# control_psw.net
KiCad netlist of a schematic drawn in EAGLE
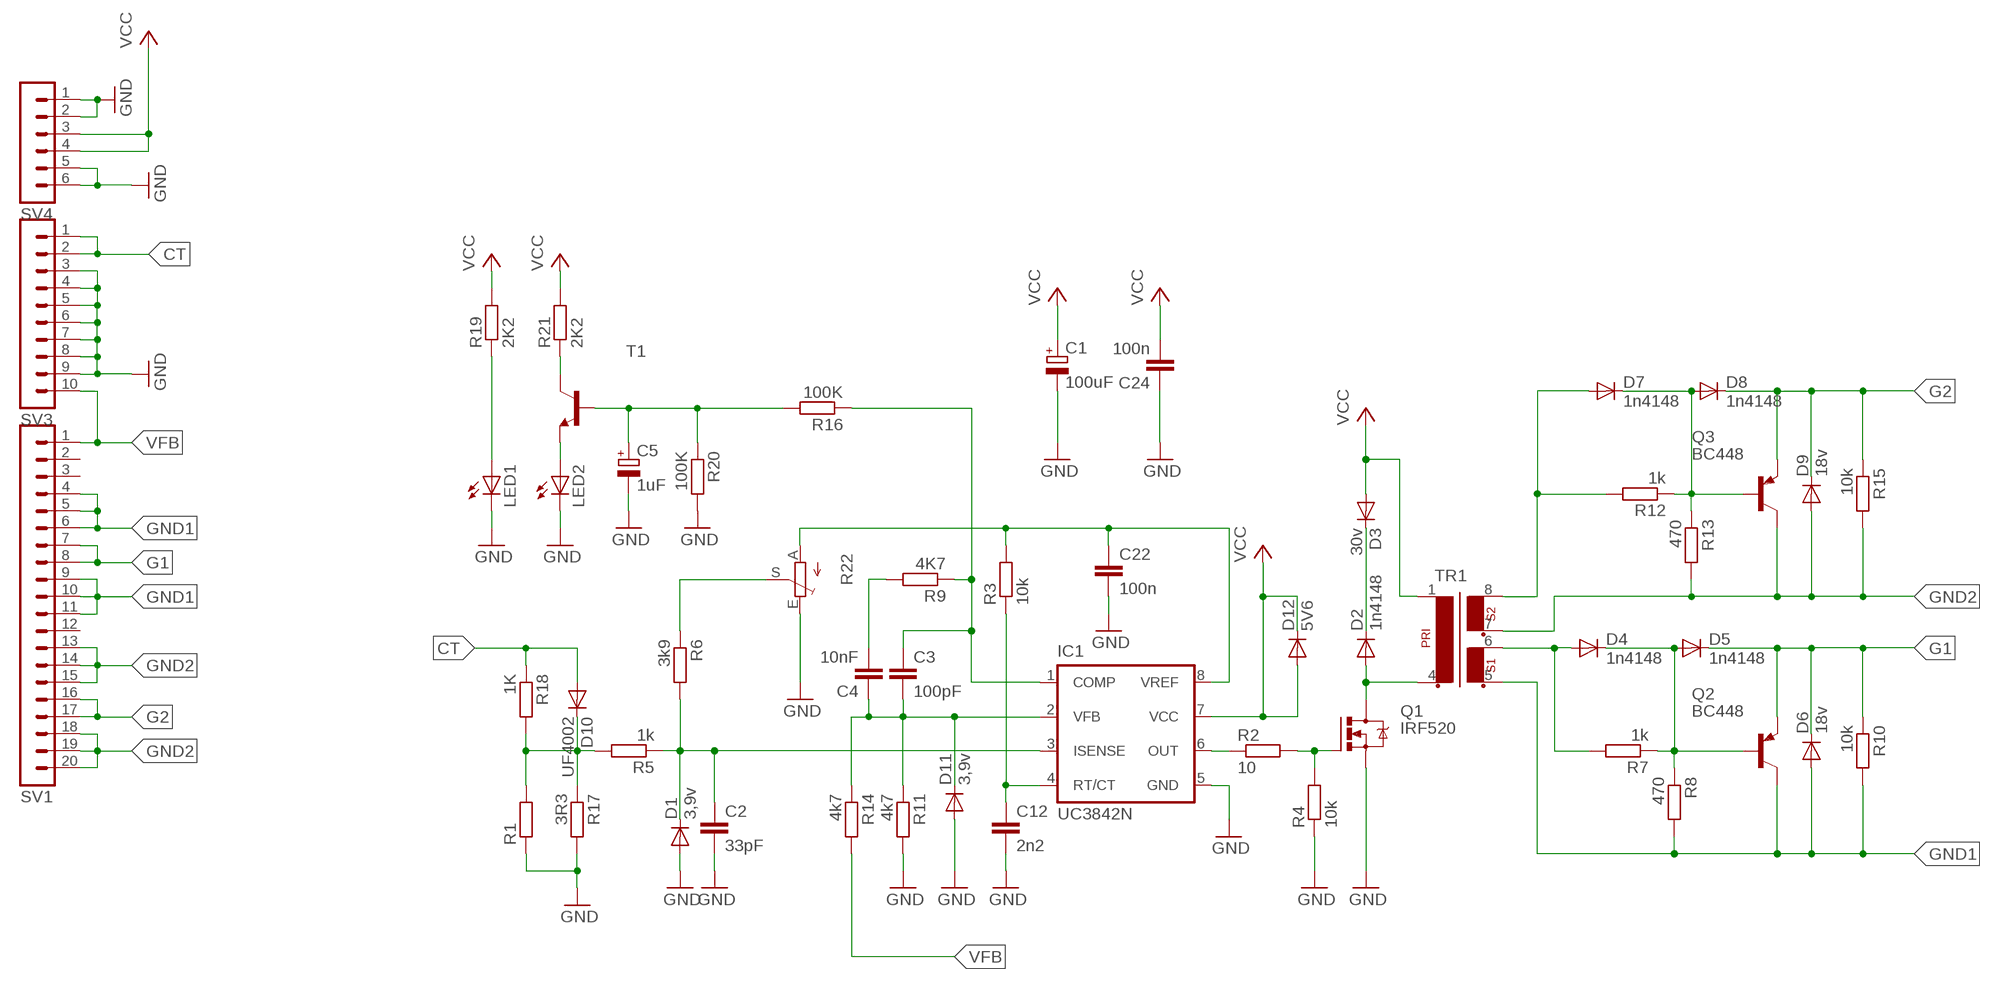
[diagram p0: schematic, sheet 1]

(export (version "E")
  (design (tool "Eeschema 10.0.6"))
  (components
    (comp (ref "C1")
      (value "100uF")
      (footprint "eagle-import:E5-6")
      (libsource (lib "eagle-import") (part "CPOL-EUE5-6"))
    )
    (comp (ref "C2")
      (value "33pF")
      (footprint "eagle-import:C050-025X075")
      (libsource (lib "eagle-import") (part "C-EU050-025X075"))
    )
    (comp (ref "C3")
      (value "100pF")
      (footprint "eagle-import:C050-025X075")
      (libsource (lib "eagle-import") (part "C-EU050-025X075"))
    )
    (comp (ref "C4")
      (value "10nF")
      (footprint "eagle-import:C050-025X075")
      (libsource (lib "eagle-import") (part "C-EU050-025X075"))
    )
    (comp (ref "C5")
      (value "1uF")
      (footprint "eagle-import:E5-6")
      (libsource (lib "eagle-import") (part "CPOL-EUE5-6"))
    )
    (comp (ref "C12")
      (value "2n2")
      (footprint "eagle-import:C050-025X075")
      (libsource (lib "eagle-import") (part "C-EU050-025X075"))
    )
    (comp (ref "C22")
      (value "100n")
      (footprint "eagle-import:C050-025X075")
      (libsource (lib "eagle-import") (part "C-EU050-025X075"))
    )
    (comp (ref "C24")
      (value "100n")
      (footprint "eagle-import:C050-025X075")
      (libsource (lib "eagle-import") (part "C-EU050-025X075"))
    )
    (comp (ref "D1")
      (value "3,9v")
      (footprint "eagle-import:DO35-10")
      (libsource (lib "eagle-import") (part "1N4446"))
    )
    (comp (ref "D2")
      (value "1n4148")
      (footprint "eagle-import:DO35-10")
      (libsource (lib "eagle-import") (part "1N4446"))
    )
    (comp (ref "D3")
      (value "30v")
      (footprint "eagle-import:DO35-10")
      (libsource (lib "eagle-import") (part "1N4446"))
    )
    (comp (ref "D4")
      (value "1n4148")
      (footprint "eagle-import:DO35-10")
      (libsource (lib "eagle-import") (part "1N4446"))
    )
    (comp (ref "D5")
      (value "1n4148")
      (footprint "eagle-import:DO35-10")
      (libsource (lib "eagle-import") (part "1N4446"))
    )
    (comp (ref "D6")
      (value "18v")
      (footprint "eagle-import:DO35-10")
      (libsource (lib "eagle-import") (part "1N4446"))
    )
    (comp (ref "D7")
      (value "1n4148")
      (footprint "eagle-import:DO35-10")
      (libsource (lib "eagle-import") (part "1N4446"))
    )
    (comp (ref "D8")
      (value "1n4148")
      (footprint "eagle-import:DO35-10")
      (libsource (lib "eagle-import") (part "1N4446"))
    )
    (comp (ref "D9")
      (value "18v")
      (footprint "eagle-import:DO35-10")
      (libsource (lib "eagle-import") (part "1N4446"))
    )
    (comp (ref "D10")
      (value "UF4002")
      (footprint "eagle-import:DO35-10")
      (libsource (lib "eagle-import") (part "1N4446"))
    )
    (comp (ref "D11")
      (value "3,9v")
      (footprint "eagle-import:DO35-10")
      (libsource (lib "eagle-import") (part "1N4446"))
    )
    (comp (ref "D12")
      (value "5V6")
      (footprint "eagle-import:DO35-10")
      (libsource (lib "eagle-import") (part "1N4446"))
    )
    (comp (ref "IC1")
      (value "UC3842N")
      (footprint "eagle-import:DIL08")
      (libsource (lib "eagle-import") (part "UC384N2"))
    )
    (comp (ref "LED1")
      (value "LED5MM")
      (footprint "eagle-import:LED5MM")
      (libsource (lib "eagle-import") (part "LED5MM"))
    )
    (comp (ref "LED2")
      (value "LED5MM")
      (footprint "eagle-import:LED5MM")
      (libsource (lib "eagle-import") (part "LED5MM"))
    )
    (comp (ref "Q1")
      (value "IRF520")
      (footprint "eagle-import:TO220BV")
      (libsource (lib "eagle-import") (part "IRF520"))
    )
    (comp (ref "Q2")
      (value "BC448")
      (footprint "eagle-import:TO92-EBC")
      (libsource (lib "eagle-import") (part "BC448"))
    )
    (comp (ref "Q3")
      (value "BC448")
      (footprint "eagle-import:TO92-EBC")
      (libsource (lib "eagle-import") (part "BC448"))
    )
    (comp (ref "R1")
      (value "R-EU_0411/12")
      (footprint "eagle-import:0411_12")
      (libsource (lib "eagle-import") (part "R-EU_0411/12"))
    )
    (comp (ref "R2")
      (value "10")
      (footprint "eagle-import:0207_10")
      (libsource (lib "eagle-import") (part "R-EU_0207/10"))
    )
    (comp (ref "R3")
      (value "10k")
      (footprint "eagle-import:0207_10")
      (libsource (lib "eagle-import") (part "R-EU_0207/10"))
    )
    (comp (ref "R4")
      (value "10k")
      (footprint "eagle-import:0207_10")
      (libsource (lib "eagle-import") (part "R-EU_0207/10"))
    )
    (comp (ref "R5")
      (value "1k")
      (footprint "eagle-import:0207_10")
      (libsource (lib "eagle-import") (part "R-EU_0207/10"))
    )
    (comp (ref "R6")
      (value "3k9")
      (footprint "eagle-import:0207_10")
      (libsource (lib "eagle-import") (part "R-EU_0207/10"))
    )
    (comp (ref "R7")
      (value "1k")
      (footprint "eagle-import:0207_10")
      (libsource (lib "eagle-import") (part "R-EU_0207/10"))
    )
    (comp (ref "R8")
      (value "470")
      (footprint "eagle-import:0207_10")
      (libsource (lib "eagle-import") (part "R-EU_0207/10"))
    )
    (comp (ref "R9")
      (value "4K7")
      (footprint "eagle-import:0207_10")
      (libsource (lib "eagle-import") (part "R-EU_0207/10"))
    )
    (comp (ref "R10")
      (value "10k")
      (footprint "eagle-import:0207_10")
      (libsource (lib "eagle-import") (part "R-EU_0207/10"))
    )
    (comp (ref "R11")
      (value "4k7")
      (footprint "eagle-import:0207_10")
      (libsource (lib "eagle-import") (part "R-EU_0207/10"))
    )
    (comp (ref "R12")
      (value "1k")
      (footprint "eagle-import:0207_10")
      (libsource (lib "eagle-import") (part "R-EU_0207/10"))
    )
    (comp (ref "R13")
      (value "470")
      (footprint "eagle-import:0207_10")
      (libsource (lib "eagle-import") (part "R-EU_0207/10"))
    )
    (comp (ref "R14")
      (value "4k7")
      (footprint "eagle-import:0207_10")
      (libsource (lib "eagle-import") (part "R-EU_0207/10"))
    )
    (comp (ref "R15")
      (value "10k")
      (footprint "eagle-import:0207_10")
      (libsource (lib "eagle-import") (part "R-EU_0207/10"))
    )
    (comp (ref "R16")
      (value "100K")
      (footprint "eagle-import:0207_10")
      (libsource (lib "eagle-import") (part "R-EU_0207/10"))
    )
    (comp (ref "R17")
      (value "3R3")
      (footprint "eagle-import:0207_10")
      (libsource (lib "eagle-import") (part "R-EU_0207/10"))
    )
    (comp (ref "R18")
      (value "1K")
      (footprint "eagle-import:0207_10")
      (libsource (lib "eagle-import") (part "R-EU_0207/10"))
    )
    (comp (ref "R19")
      (value "2K2")
      (footprint "eagle-import:0207_10")
      (libsource (lib "eagle-import") (part "R-EU_0207/10"))
    )
    (comp (ref "R20")
      (value "100K")
      (footprint "eagle-import:0207_10")
      (libsource (lib "eagle-import") (part "R-EU_0207/10"))
    )
    (comp (ref "R21")
      (value "2K2")
      (footprint "eagle-import:0207_10")
      (libsource (lib "eagle-import") (part "R-EU_0207/10"))
    )
    (comp (ref "R22")
      (value "TRIM_EU-RJ9W")
      (footprint "eagle-import:RJ9W")
      (libsource (lib "eagle-import") (part "TRIM_EU-RJ9W"))
    )
    (comp (ref "SV1")
      (value "MA20-1")
      (footprint "eagle-import:MA20-1")
      (libsource (lib "eagle-import") (part "MA20-1"))
    )
    (comp (ref "SV3")
      (value "MA10-1")
      (footprint "eagle-import:MA10-1")
      (libsource (lib "eagle-import") (part "MA10-1"))
    )
    (comp (ref "SV4")
      (value "MA06-1")
      (footprint "eagle-import:MA06-1")
      (libsource (lib "eagle-import") (part "MA06-1"))
    )
    (comp (ref "T1")
      (value "BC547-NPN-TO92-CBE")
      (footprint "eagle-import:TO92-CBE")
      (libsource (lib "eagle-import") (part "-NPN-TO92-CBEBC547"))
    )
    (comp (ref "TR1")
      (value "EE20-2")
      (footprint "eagle-import:EE20-2")
      (libsource (lib "eagle-import") (part "EE20-2"))
    )
  )
  (nets
    (net (code "1") (name "CT") (class "Default")
      (node (ref "D10") (pin "A") (pinfunction "A_A") (pintype "passive"))
      (node (ref "R18") (pin "1") (pinfunction "1_1") (pintype "passive"))
      (node (ref "SV3") (pin "1") (pinfunction "1_1") (pintype "passive"))
      (node (ref "SV3") (pin "2") (pinfunction "2_2") (pintype "passive"))
    )
    (net (code "2") (name "G1") (class "Default")
      (node (ref "D5") (pin "C") (pinfunction "C_C") (pintype "passive"))
      (node (ref "D6") (pin "C") (pinfunction "C_C") (pintype "passive"))
      (node (ref "Q2") (pin "E") (pinfunction "E_E") (pintype "passive"))
      (node (ref "R10") (pin "1") (pinfunction "1_1") (pintype "passive"))
      (node (ref "SV1") (pin "7") (pinfunction "7_7") (pintype "passive"))
      (node (ref "SV1") (pin "8") (pinfunction "8_8") (pintype "passive"))
    )
    (net (code "3") (name "G2") (class "Default")
      (node (ref "D8") (pin "C") (pinfunction "C_C") (pintype "passive"))
      (node (ref "D9") (pin "C") (pinfunction "C_C") (pintype "passive"))
      (node (ref "Q3") (pin "E") (pinfunction "E_E") (pintype "passive"))
      (node (ref "R15") (pin "1") (pinfunction "1_1") (pintype "passive"))
      (node (ref "SV1") (pin "16") (pinfunction "16_16") (pintype "passive"))
      (node (ref "SV1") (pin "17") (pinfunction "17_17") (pintype "passive"))
    )
    (net (code "4") (name "GND") (class "Default")
      (node (ref "C1") (pin "-") (pinfunction "-_-") (pintype "passive"))
      (node (ref "C12") (pin "2") (pinfunction "2_2") (pintype "passive"))
      (node (ref "C2") (pin "2") (pinfunction "2_2") (pintype "passive"))
      (node (ref "C22") (pin "2") (pinfunction "2_2") (pintype "passive"))
      (node (ref "C24") (pin "1") (pinfunction "1_1") (pintype "passive"))
      (node (ref "C5") (pin "-") (pinfunction "-_-") (pintype "passive"))
      (node (ref "D1") (pin "A") (pinfunction "A_A") (pintype "passive"))
      (node (ref "D11") (pin "A") (pinfunction "A_A") (pintype "passive"))
      (node (ref "IC1") (pin "5") (pinfunction "GND_5") (pintype "power_in"))
      (node (ref "LED1") (pin "K") (pinfunction "C_K") (pintype "passive"))
      (node (ref "LED2") (pin "K") (pinfunction "C_K") (pintype "passive"))
      (node (ref "Q1") (pin "S") (pinfunction "S_S") (pintype "passive"))
      (node (ref "R1") (pin "1") (pinfunction "1_1") (pintype "passive"))
      (node (ref "R11") (pin "2") (pinfunction "2_2") (pintype "passive"))
      (node (ref "R17") (pin "2") (pinfunction "2_2") (pintype "passive"))
      (node (ref "R20") (pin "2") (pinfunction "2_2") (pintype "passive"))
      (node (ref "R22") (pin "E") (pinfunction "E_E") (pintype "passive"))
      (node (ref "R4") (pin "1") (pinfunction "1_1") (pintype "passive"))
      (node (ref "SV3") (pin "3") (pinfunction "3_3") (pintype "passive"))
      (node (ref "SV3") (pin "4") (pinfunction "4_4") (pintype "passive"))
      (node (ref "SV3") (pin "5") (pinfunction "5_5") (pintype "passive"))
      (node (ref "SV3") (pin "6") (pinfunction "6_6") (pintype "passive"))
      (node (ref "SV3") (pin "7") (pinfunction "7_7") (pintype "passive"))
      (node (ref "SV3") (pin "8") (pinfunction "8_8") (pintype "passive"))
      (node (ref "SV3") (pin "9") (pinfunction "9_9") (pintype "passive"))
      (node (ref "SV4") (pin "1") (pinfunction "1_1") (pintype "passive"))
      (node (ref "SV4") (pin "2") (pinfunction "2_2") (pintype "passive"))
      (node (ref "SV4") (pin "5") (pinfunction "5_5") (pintype "passive"))
      (node (ref "SV4") (pin "6") (pinfunction "6_6") (pintype "passive"))
    )
    (net (code "5") (name "GND1") (class "Default")
      (node (ref "D6") (pin "A") (pinfunction "A_A") (pintype "passive"))
      (node (ref "Q2") (pin "C") (pinfunction "C_C") (pintype "passive"))
      (node (ref "R10") (pin "2") (pinfunction "2_2") (pintype "passive"))
      (node (ref "R8") (pin "2") (pinfunction "2_2") (pintype "passive"))
      (node (ref "SV1") (pin "10") (pinfunction "10_10") (pintype "passive"))
      (node (ref "SV1") (pin "11") (pinfunction "11_11") (pintype "passive"))
      (node (ref "SV1") (pin "4") (pinfunction "4_4") (pintype "passive"))
      (node (ref "SV1") (pin "5") (pinfunction "5_5") (pintype "passive"))
      (node (ref "SV1") (pin "6") (pinfunction "6_6") (pintype "passive"))
      (node (ref "SV1") (pin "9") (pinfunction "9_9") (pintype "passive"))
      (node (ref "TR1") (pin "5") (pinfunction "3_5") (pintype "passive"))
    )
    (net (code "6") (name "GND2") (class "Default")
      (node (ref "D9") (pin "A") (pinfunction "A_A") (pintype "passive"))
      (node (ref "Q3") (pin "C") (pinfunction "C_C") (pintype "passive"))
      (node (ref "R13") (pin "2") (pinfunction "2_2") (pintype "passive"))
      (node (ref "R15") (pin "2") (pinfunction "2_2") (pintype "passive"))
      (node (ref "SV1") (pin "13") (pinfunction "13_13") (pintype "passive"))
      (node (ref "SV1") (pin "14") (pinfunction "14_14") (pintype "passive"))
      (node (ref "SV1") (pin "15") (pinfunction "15_15") (pintype "passive"))
      (node (ref "SV1") (pin "18") (pinfunction "18_18") (pintype "passive"))
      (node (ref "SV1") (pin "19") (pinfunction "19_19") (pintype "passive"))
      (node (ref "SV1") (pin "20") (pinfunction "20_20") (pintype "passive"))
      (node (ref "TR1") (pin "7") (pinfunction "5_7") (pintype "passive"))
    )
    (net (code "7") (name "Net-(C4-Pad2)") (class "Default")
      (node (ref "C4") (pin "2") (pinfunction "2_2") (pintype "passive"))
      (node (ref "R9") (pin "2") (pinfunction "2_2") (pintype "passive"))
    )
    (net (code "8") (name "Net-(C5-Pad+)") (class "Default")
      (node (ref "C5") (pin "+") (pinfunction "+_+") (pintype "passive"))
      (node (ref "R16") (pin "2") (pinfunction "2_2") (pintype "passive"))
      (node (ref "R20") (pin "1") (pinfunction "1_1") (pintype "passive"))
      (node (ref "T1") (pin "B") (pinfunction "B_B") (pintype "passive"))
    )
    (net (code "9") (name "Net-(D2-PadC)") (class "Default")
      (node (ref "D2") (pin "C") (pinfunction "C_C") (pintype "passive"))
      (node (ref "D3") (pin "C") (pinfunction "C_C") (pintype "passive"))
    )
    (net (code "10") (name "Net-(D4-PadC)") (class "Default")
      (node (ref "D4") (pin "C") (pinfunction "C_C") (pintype "passive"))
      (node (ref "D5") (pin "A") (pinfunction "A_A") (pintype "passive"))
      (node (ref "Q2") (pin "B") (pinfunction "B_B") (pintype "passive"))
      (node (ref "R7") (pin "1") (pinfunction "1_1") (pintype "passive"))
      (node (ref "R8") (pin "1") (pinfunction "1_1") (pintype "passive"))
    )
    (net (code "11") (name "Net-(D7-PadC)") (class "Default")
      (node (ref "D7") (pin "C") (pinfunction "C_C") (pintype "passive"))
      (node (ref "D8") (pin "A") (pinfunction "A_A") (pintype "passive"))
      (node (ref "Q3") (pin "B") (pinfunction "B_B") (pintype "passive"))
      (node (ref "R12") (pin "1") (pinfunction "1_1") (pintype "passive"))
      (node (ref "R13") (pin "1") (pinfunction "1_1") (pintype "passive"))
    )
    (net (code "12") (name "Net-(D10-PadC)") (class "Default")
      (node (ref "D10") (pin "C") (pinfunction "C_C") (pintype "passive"))
      (node (ref "R1") (pin "2") (pinfunction "2_2") (pintype "passive"))
      (node (ref "R17") (pin "1") (pinfunction "1_1") (pintype "passive"))
      (node (ref "R18") (pin "2") (pinfunction "2_2") (pintype "passive"))
      (node (ref "R5") (pin "2") (pinfunction "2_2") (pintype "passive"))
    )
    (net (code "13") (name "Net-(IC1-COMP)") (class "Default")
      (node (ref "C3") (pin "1") (pinfunction "1_1") (pintype "passive"))
      (node (ref "IC1") (pin "1") (pinfunction "COMP_1") (pintype "passive"))
      (node (ref "R16") (pin "1") (pinfunction "1_1") (pintype "passive"))
      (node (ref "R9") (pin "1") (pinfunction "1_1") (pintype "passive"))
    )
    (net (code "14") (name "Net-(IC1-ISENSE)") (class "Default")
      (node (ref "C2") (pin "1") (pinfunction "1_1") (pintype "passive"))
      (node (ref "D1") (pin "C") (pinfunction "C_C") (pintype "passive"))
      (node (ref "IC1") (pin "3") (pinfunction "ISENSE_3") (pintype "input"))
      (node (ref "R5") (pin "1") (pinfunction "1_1") (pintype "passive"))
      (node (ref "R6") (pin "2") (pinfunction "2_2") (pintype "passive"))
    )
    (net (code "15") (name "Net-(IC1-OUT)") (class "Default")
      (node (ref "IC1") (pin "6") (pinfunction "OUT_6") (pintype "output"))
      (node (ref "R2") (pin "1") (pinfunction "1_1") (pintype "passive"))
    )
    (net (code "16") (name "Net-(IC1-RT{slash}CT)") (class "Default")
      (node (ref "C12") (pin "1") (pinfunction "1_1") (pintype "passive"))
      (node (ref "IC1") (pin "4") (pinfunction "RT/CT_4") (pintype "passive"))
      (node (ref "R3") (pin "1") (pinfunction "1_1") (pintype "passive"))
    )
    (net (code "17") (name "Net-(IC1-VFB)") (class "Default")
      (node (ref "C3") (pin "2") (pinfunction "2_2") (pintype "passive"))
      (node (ref "C4") (pin "1") (pinfunction "1_1") (pintype "passive"))
      (node (ref "D11") (pin "C") (pinfunction "C_C") (pintype "passive"))
      (node (ref "IC1") (pin "2") (pinfunction "VFB_2") (pintype "input"))
      (node (ref "R11") (pin "1") (pinfunction "1_1") (pintype "passive"))
      (node (ref "R14") (pin "1") (pinfunction "1_1") (pintype "passive"))
    )
    (net (code "18") (name "Net-(IC1-VREF)") (class "Default")
      (node (ref "C22") (pin "1") (pinfunction "1_1") (pintype "passive"))
      (node (ref "IC1") (pin "8") (pinfunction "VREF_8") (pintype "passive"))
      (node (ref "R22") (pin "A") (pinfunction "A_A") (pintype "passive"))
      (node (ref "R3") (pin "2") (pinfunction "2_2") (pintype "passive"))
    )
    (net (code "19") (name "Net-(LED1-PadA)") (class "Default")
      (node (ref "LED1") (pin "A") (pinfunction "A_A") (pintype "passive"))
      (node (ref "R19") (pin "1") (pinfunction "1_1") (pintype "passive"))
    )
    (net (code "20") (name "Net-(LED2-PadA)") (class "Default")
      (node (ref "LED2") (pin "A") (pinfunction "A_A") (pintype "passive"))
      (node (ref "T1") (pin "E") (pinfunction "E_E") (pintype "passive"))
    )
    (net (code "21") (name "Net-(Q1-PadG)") (class "Default")
      (node (ref "Q1") (pin "G") (pinfunction "G_G") (pintype "passive"))
      (node (ref "R2") (pin "2") (pinfunction "2_2") (pintype "passive"))
      (node (ref "R4") (pin "2") (pinfunction "2_2") (pintype "passive"))
    )
    (net (code "22") (name "Net-(R21-Pad1)") (class "Default")
      (node (ref "R21") (pin "1") (pinfunction "1_1") (pintype "passive"))
      (node (ref "T1") (pin "C") (pinfunction "C_C") (pintype "passive"))
    )
    (net (code "23") (name "Net-(R22-PadS)") (class "Default")
      (node (ref "R22") (pin "S") (pinfunction "S_S") (pintype "passive"))
      (node (ref "R6") (pin "1") (pinfunction "1_1") (pintype "passive"))
    )
    (net (code "24") (name "Net-(TR1-2)") (class "Default")
      (node (ref "D2") (pin "A") (pinfunction "A_A") (pintype "passive"))
      (node (ref "Q1") (pin "D") (pinfunction "D_D") (pintype "passive"))
      (node (ref "TR1") (pin "4") (pinfunction "2_4") (pintype "passive"))
    )
    (net (code "25") (name "Net-(TR1-4)") (class "Default")
      (node (ref "D4") (pin "A") (pinfunction "A_A") (pintype "passive"))
      (node (ref "R7") (pin "2") (pinfunction "2_2") (pintype "passive"))
      (node (ref "TR1") (pin "6") (pinfunction "4_6") (pintype "passive"))
    )
    (net (code "26") (name "Net-(TR1-6)") (class "Default")
      (node (ref "D7") (pin "A") (pinfunction "A_A") (pintype "passive"))
      (node (ref "R12") (pin "2") (pinfunction "2_2") (pintype "passive"))
      (node (ref "TR1") (pin "8") (pinfunction "6_8") (pintype "passive"))
    )
    (net (code "27") (name "VCC") (class "Default")
      (node (ref "C1") (pin "+") (pinfunction "+_+") (pintype "passive"))
      (node (ref "C24") (pin "2") (pinfunction "2_2") (pintype "passive"))
      (node (ref "D12") (pin "A") (pinfunction "A_A") (pintype "passive"))
      (node (ref "D12") (pin "C") (pinfunction "C_C") (pintype "passive"))
      (node (ref "D3") (pin "A") (pinfunction "A_A") (pintype "passive"))
      (node (ref "IC1") (pin "7") (pinfunction "VCC_7") (pintype "power_in"))
      (node (ref "R19") (pin "2") (pinfunction "2_2") (pintype "passive"))
      (node (ref "R21") (pin "2") (pinfunction "2_2") (pintype "passive"))
      (node (ref "SV4") (pin "3") (pinfunction "3_3") (pintype "passive"))
      (node (ref "SV4") (pin "4") (pinfunction "4_4") (pintype "passive"))
      (node (ref "TR1") (pin "1") (pinfunction "1_1") (pintype "passive"))
    )
    (net (code "28") (name "VFB") (class "Default")
      (node (ref "R14") (pin "2") (pinfunction "2_2") (pintype "passive"))
      (node (ref "SV1") (pin "1") (pinfunction "1_1") (pintype "passive"))
      (node (ref "SV3") (pin "10") (pinfunction "10_10") (pintype "passive"))
    )
    (net (code "29") (name "unconnected-(SV1-Pad2)") (class "Default")
      (node (ref "SV1") (pin "2") (pinfunction "2_2") (pintype "passive"))
    )
    (net (code "30") (name "unconnected-(SV1-Pad3)") (class "Default")
      (node (ref "SV1") (pin "3") (pinfunction "3_3") (pintype "passive"))
    )
    (net (code "31") (name "unconnected-(SV1-Pad12)") (class "Default")
      (node (ref "SV1") (pin "12") (pinfunction "12_12") (pintype "passive"))
    )
  )
)
